# example.net
KiCad netlist of a schematic drawn in EAGLE
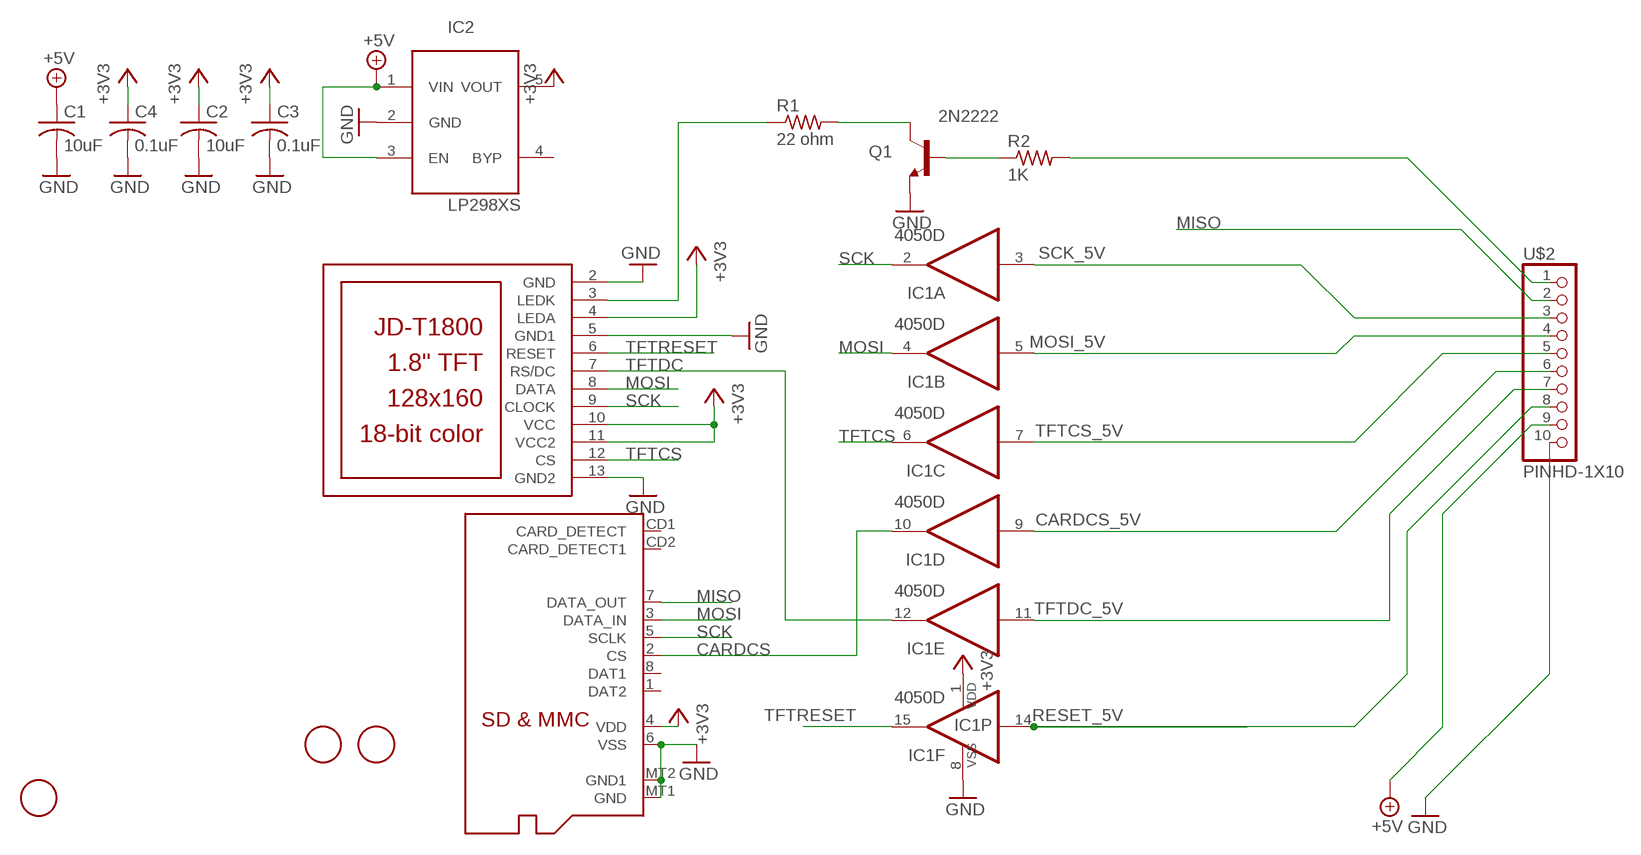
[diagram p0: schematic, sheet 1]

(export (version "E")
  (design (tool "Eeschema 10.0.6"))
  (components
    (comp (ref "C1")
      (value "10uF")
      (footprint "eagle-import:C0805K")
      (libsource (lib "eagle-import") (part "C-USC0805K"))
    )
    (comp (ref "C2")
      (value "10uF")
      (footprint "eagle-import:C0805K")
      (libsource (lib "eagle-import") (part "C-USC0805K"))
    )
    (comp (ref "C3")
      (value "0.1uF")
      (footprint "eagle-import:C0805K")
      (libsource (lib "eagle-import") (part "C-USC0805K"))
    )
    (comp (ref "C4")
      (value "0.1uF")
      (footprint "eagle-import:C0805K")
      (libsource (lib "eagle-import") (part "C-USC0805K"))
    )
    (comp (ref "IC1")
      (value "4050D")
      (footprint "eagle-import:SO16")
      (libsource (lib "eagle-import") (part "4050D"))
    )
    (comp (ref "IC2")
      (value "LP298XS")
      (footprint "eagle-import:SOT23-5L")
      (libsource (lib "eagle-import") (part "LP298XS"))
    )
    (comp (ref "Q1")
      (value "2N2222")
      (footprint "eagle-import:SOT23-BEC")
      (libsource (lib "eagle-import") (part "-NPN-SOT23-BECMMBT2222ALT1"))
    )
    (comp (ref "Q2")
      (value "MICROSD")
      (footprint "eagle-import:MICROSD")
      (libsource (lib "eagle-import") (part "MICROSD"))
    )
    (comp (ref "R1")
      (value "22 ohm")
      (footprint "eagle-import:R0805")
      (libsource (lib "eagle-import") (part "R-US_R0805"))
    )
    (comp (ref "R2")
      (value "1K")
      (footprint "eagle-import:R0805")
      (libsource (lib "eagle-import") (part "R-US_R0805"))
    )
    (comp (ref "U$1")
      (value "JD-T1800")
      (footprint "eagle-import:JD-T1800")
      (libsource (lib "eagle-import") (part "JD-T1800"))
    )
    (comp (ref "U$2")
      (value "PINHD-1X10")
      (footprint "eagle-import:1X10-BIG")
      (libsource (lib "eagle-import") (part "PINHD-1X10"))
    )
    (comp (ref "U$3")
      (value "FIDUCIAL")
      (footprint "eagle-import:FIDUCIAL_1MM")
      (libsource (lib "eagle-import") (part "FIDUCIAL"))
    )
    (comp (ref "U$4")
      (value "FIDUCIAL")
      (footprint "eagle-import:FIDUCIAL_1MM")
      (libsource (lib "eagle-import") (part "FIDUCIAL"))
    )
    (comp (ref "U$5")
      (value "FIDUCIAL")
      (footprint "eagle-import:FIDUCIAL_1MM")
      (libsource (lib "eagle-import") (part "FIDUCIAL"))
    )
  )
  (nets
    (net (code "1") (name "+3V3") (class "Default")
      (node (ref "C2") (pin "1") (pinfunction "1_1") (pintype "passive"))
      (node (ref "C3") (pin "1") (pinfunction "1_1") (pintype "passive"))
      (node (ref "C4") (pin "1") (pinfunction "1_1") (pintype "passive"))
      (node (ref "IC1") (pin "1") (pinfunction "VDD_1") (pintype "power_in"))
      (node (ref "IC2") (pin "5") (pinfunction "VOUT_5") (pintype "bidirectional"))
      (node (ref "Q2") (pin "4") (pinfunction "VDD_4") (pintype "power_in"))
      (node (ref "U$1") (pin "10") (pinfunction "VCC_10") (pintype "power_in"))
      (node (ref "U$1") (pin "11") (pinfunction "VCC2_11") (pintype "power_in"))
      (node (ref "U$1") (pin "4") (pinfunction "LEDA_4") (pintype "input"))
    )
    (net (code "2") (name "+5V") (class "Default")
      (node (ref "C1") (pin "1") (pinfunction "1_1") (pintype "passive"))
      (node (ref "IC2") (pin "1") (pinfunction "VIN_1") (pintype "bidirectional"))
      (node (ref "IC2") (pin "3") (pinfunction "EN_3") (pintype "bidirectional"))
      (node (ref "U$2") (pin "9") (pinfunction "9_9") (pintype "passive"))
    )
    (net (code "3") (name "/CARDCS") (class "Default")
      (node (ref "IC1") (pin "10") (pinfunction "O_10") (pintype "output"))
      (node (ref "Q2") (pin "2") (pinfunction "CS_2") (pintype "input"))
    )
    (net (code "4") (name "/CARDCS_5V") (class "Default")
      (node (ref "IC1") (pin "9") (pinfunction "I_9") (pintype "input"))
      (node (ref "U$2") (pin "6") (pinfunction "6_6") (pintype "passive"))
    )
    (net (code "5") (name "/MISO") (class "Default")
      (node (ref "Q2") (pin "7") (pinfunction "DATA_OUT_7") (pintype "output"))
      (node (ref "U$2") (pin "2") (pinfunction "2_2") (pintype "passive"))
    )
    (net (code "6") (name "/MOSI") (class "Default")
      (node (ref "IC1") (pin "4") (pinfunction "O_4") (pintype "output"))
      (node (ref "Q2") (pin "3") (pinfunction "DATA_IN_3") (pintype "input"))
      (node (ref "U$1") (pin "8") (pinfunction "DATA_8") (pintype "bidirectional"))
    )
    (net (code "7") (name "/MOSI_5V") (class "Default")
      (node (ref "IC1") (pin "5") (pinfunction "I_5") (pintype "input"))
      (node (ref "U$2") (pin "4") (pinfunction "4_4") (pintype "passive"))
    )
    (net (code "8") (name "/RESET_5V") (class "Default")
      (node (ref "IC1") (pin "14") (pinfunction "I_14") (pintype "input"))
      (node (ref "U$2") (pin "8") (pinfunction "8_8") (pintype "passive"))
    )
    (net (code "9") (name "/SCK") (class "Default")
      (node (ref "IC1") (pin "2") (pinfunction "O_2") (pintype "output"))
      (node (ref "Q2") (pin "5") (pinfunction "SCLK_5") (pintype "input"))
      (node (ref "U$1") (pin "9") (pinfunction "CLOCK_9") (pintype "input"))
    )
    (net (code "10") (name "/SCK_5V") (class "Default")
      (node (ref "IC1") (pin "3") (pinfunction "I_3") (pintype "input"))
      (node (ref "U$2") (pin "3") (pinfunction "3_3") (pintype "passive"))
    )
    (net (code "11") (name "/TFTCS") (class "Default")
      (node (ref "IC1") (pin "6") (pinfunction "O_6") (pintype "output"))
      (node (ref "U$1") (pin "12") (pinfunction "CS_12") (pintype "input"))
    )
    (net (code "12") (name "/TFTCS_5V") (class "Default")
      (node (ref "IC1") (pin "7") (pinfunction "I_7") (pintype "input"))
      (node (ref "U$2") (pin "5") (pinfunction "5_5") (pintype "passive"))
    )
    (net (code "13") (name "/TFTDC") (class "Default")
      (node (ref "IC1") (pin "12") (pinfunction "O_12") (pintype "output"))
      (node (ref "U$1") (pin "7") (pinfunction "RS/DC_7") (pintype "input"))
    )
    (net (code "14") (name "/TFTDC_5V") (class "Default")
      (node (ref "IC1") (pin "11") (pinfunction "I_11") (pintype "input"))
      (node (ref "U$2") (pin "7") (pinfunction "7_7") (pintype "passive"))
    )
    (net (code "15") (name "/TFTRESET") (class "Default")
      (node (ref "IC1") (pin "15") (pinfunction "O_15") (pintype "output"))
      (node (ref "U$1") (pin "6") (pinfunction "RESET_6") (pintype "input"))
    )
    (net (code "16") (name "GND") (class "Default")
      (node (ref "C1") (pin "2") (pinfunction "2_2") (pintype "passive"))
      (node (ref "C2") (pin "2") (pinfunction "2_2") (pintype "passive"))
      (node (ref "C3") (pin "2") (pinfunction "2_2") (pintype "passive"))
      (node (ref "C4") (pin "2") (pinfunction "2_2") (pintype "passive"))
      (node (ref "IC1") (pin "8") (pinfunction "VSS_8") (pintype "power_in"))
      (node (ref "IC2") (pin "2") (pinfunction "GND_2") (pintype "bidirectional"))
      (node (ref "Q1") (pin "E") (pinfunction "E_E") (pintype "passive"))
      (node (ref "Q2") (pin "6") (pinfunction "VSS_6") (pintype "power_in"))
      (node (ref "Q2") (pin "MT1") (pinfunction "GND_MT1") (pintype "power_in"))
      (node (ref "Q2") (pin "MT2") (pinfunction "GND1_MT2") (pintype "power_in"))
      (node (ref "U$1") (pin "13") (pinfunction "GND2_13") (pintype "power_in"))
      (node (ref "U$1") (pin "2") (pinfunction "GND_2") (pintype "power_in"))
      (node (ref "U$1") (pin "5") (pinfunction "GND1_5") (pintype "power_in"))
      (node (ref "U$2") (pin "10") (pinfunction "10_10") (pintype "passive"))
    )
    (net (code "17") (name "Net-(Q1-PadB)") (class "Default")
      (node (ref "Q1") (pin "B") (pinfunction "B_B") (pintype "passive"))
      (node (ref "R2") (pin "1") (pinfunction "1_1") (pintype "passive"))
    )
    (net (code "18") (name "Net-(Q1-PadC)") (class "Default")
      (node (ref "Q1") (pin "C") (pinfunction "C_C") (pintype "passive"))
      (node (ref "R1") (pin "2") (pinfunction "2_2") (pintype "passive"))
    )
    (net (code "19") (name "Net-(R2-Pad2)") (class "Default")
      (node (ref "R2") (pin "2") (pinfunction "2_2") (pintype "passive"))
      (node (ref "U$2") (pin "1") (pinfunction "1_1") (pintype "passive"))
    )
    (net (code "20") (name "Net-(U$1-LEDK)") (class "Default")
      (node (ref "R1") (pin "1") (pinfunction "1_1") (pintype "passive"))
      (node (ref "U$1") (pin "3") (pinfunction "LEDK_3") (pintype "input"))
    )
    (net (code "21") (name "unconnected-(IC2-BYP-Pad4)") (class "Default")
      (node (ref "IC2") (pin "4") (pinfunction "BYP_4") (pintype "bidirectional"))
    )
    (net (code "22") (name "unconnected-(Q2-CARD_DETECT-PadCD1)") (class "Default")
      (node (ref "Q2") (pin "CD1") (pinfunction "CARD_DETECT_CD1") (pintype "passive"))
    )
    (net (code "23") (name "unconnected-(Q2-CARD_DETECT1-PadCD2)") (class "Default")
      (node (ref "Q2") (pin "CD2") (pinfunction "CARD_DETECT1_CD2") (pintype "passive"))
    )
    (net (code "24") (name "unconnected-(Q2-DAT1-Pad8)") (class "Default")
      (node (ref "Q2") (pin "8") (pinfunction "DAT1_8") (pintype "bidirectional"))
    )
    (net (code "25") (name "unconnected-(Q2-DAT2-Pad1)") (class "Default")
      (node (ref "Q2") (pin "1") (pinfunction "DAT2_1") (pintype "bidirectional"))
    )
  )
)
